# Peripherals.net
KiCad netlist of a schematic drawn in Altium Designer
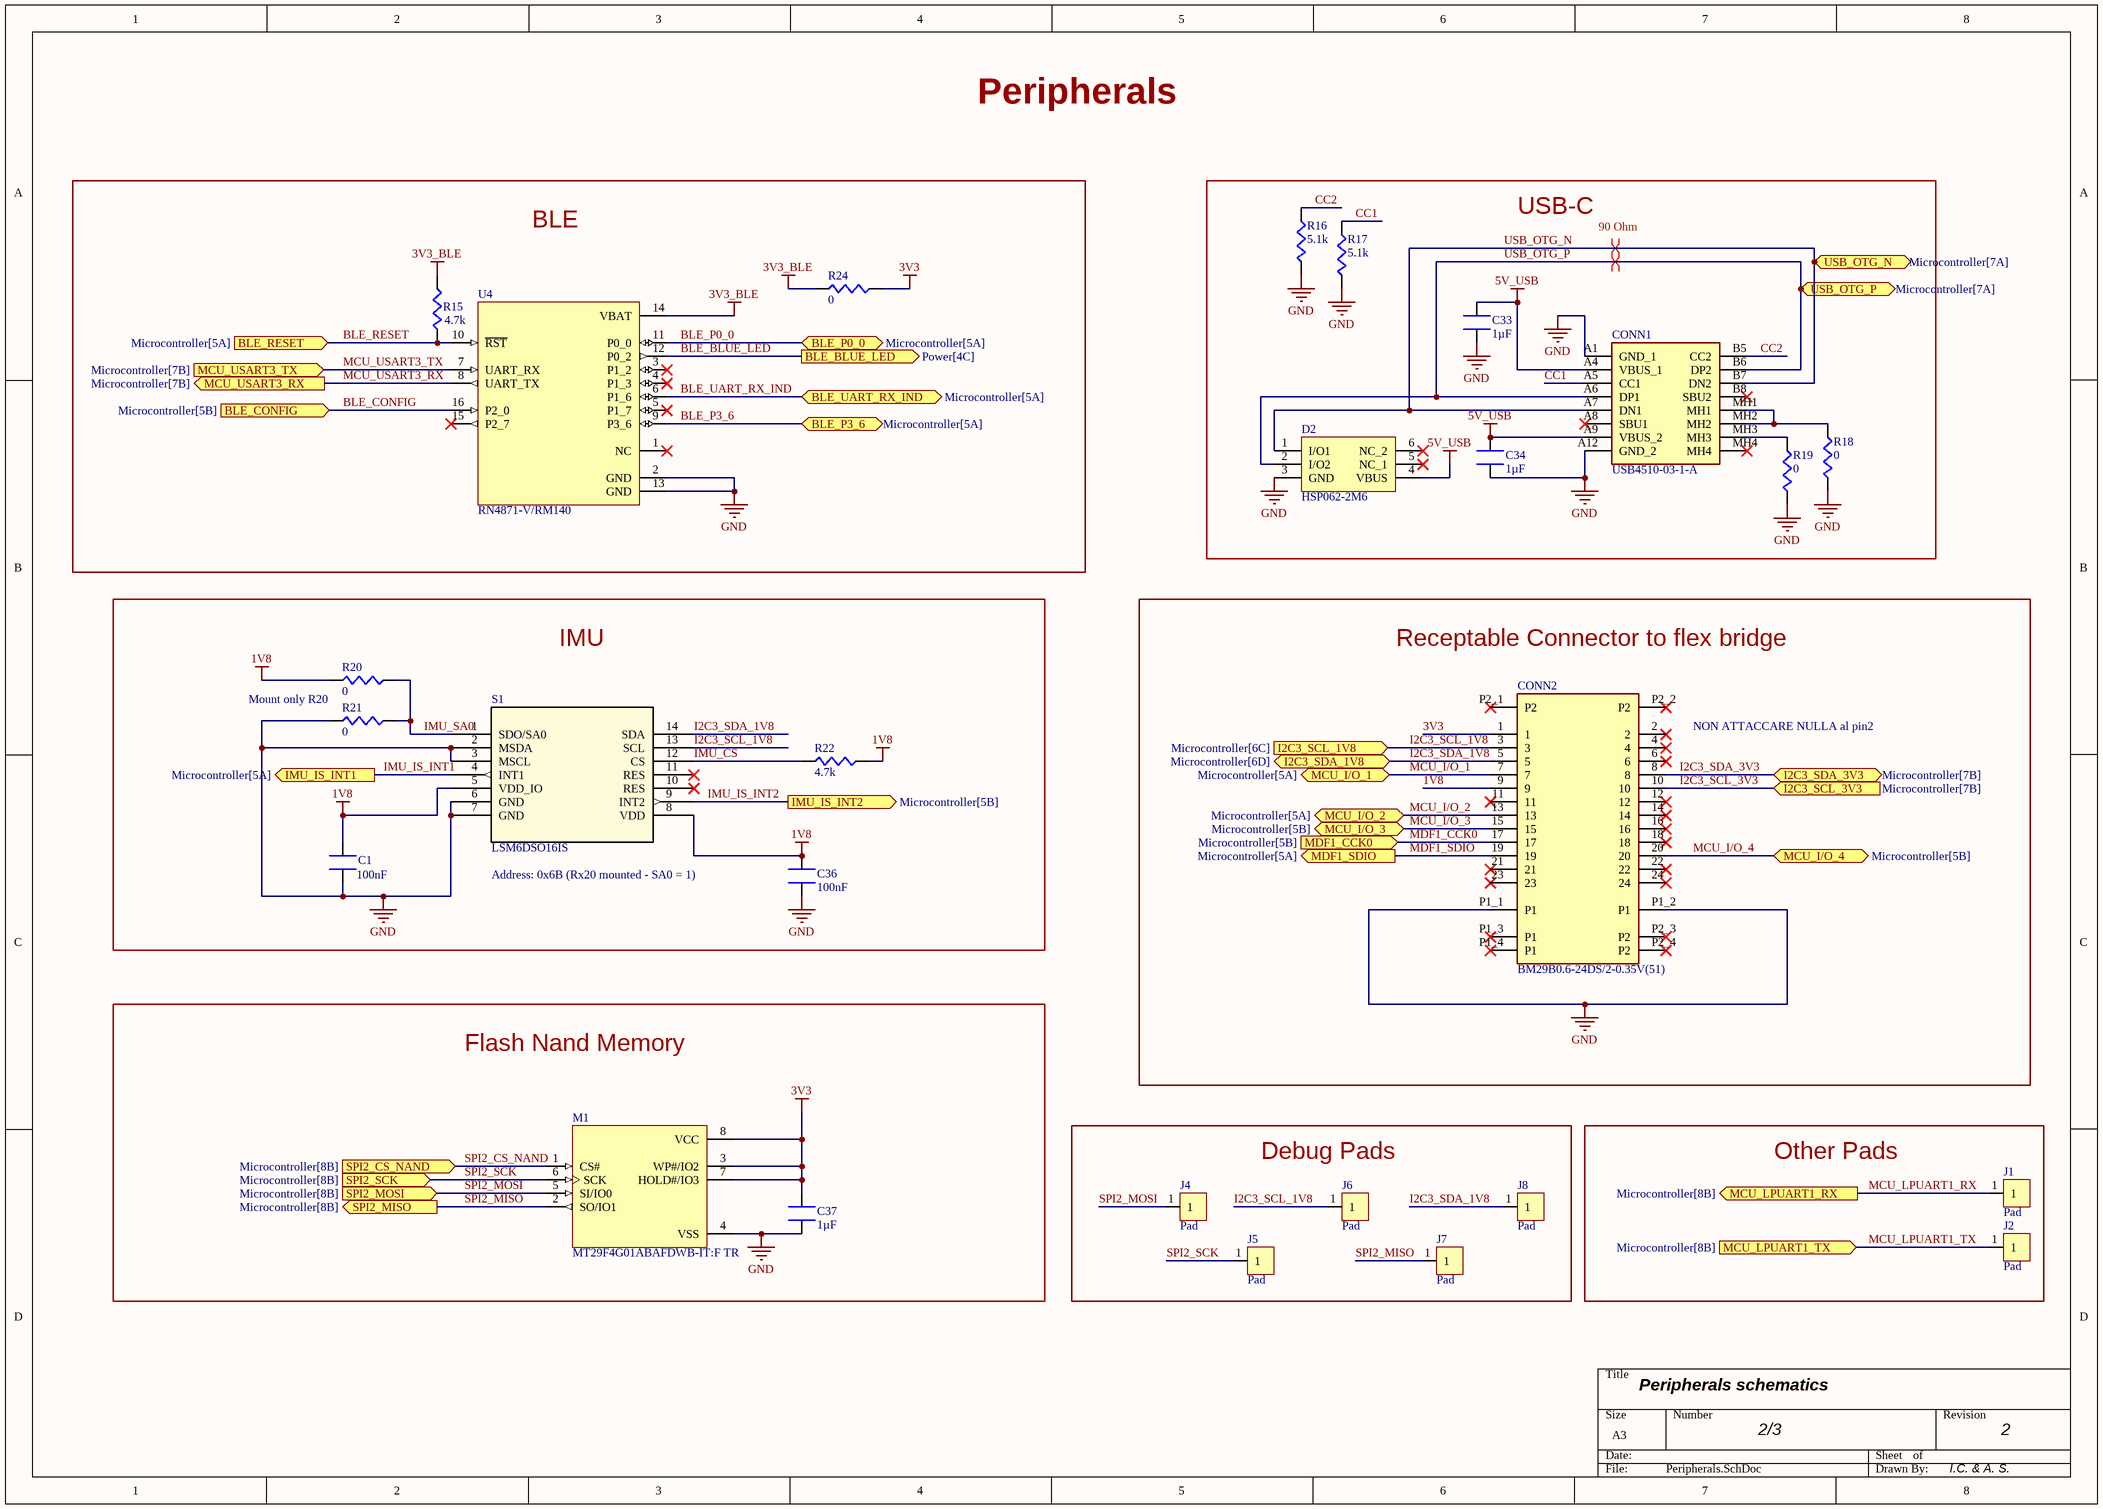
[diagram p0: Peripherals.SchDoc]

(export (version "E")
  (design (tool "Eeschema 10.0.6"))
  (components
    (comp (ref "C1")
      (value "100nF")
      (footprint "Chip2PinSM127P600-8N")
      (fields (field (name "Comment") "0201ZD104KAT2A"))
      (libsource (lib "Workspace LAB SEL") (part "Generic capacitor"))
    )
    (comp (ref "C33")
      (value "1µF")
      (footprint "Chip2PinSM127P600-8N")
      (fields (field (name "Comment") "CL03A105KP3NSNC"))
      (libsource (lib "Workspace LAB SEL") (part "Generic capacitor"))
    )
    (comp (ref "C34")
      (value "1µF")
      (footprint "Chip2PinSM127P600-8N")
      (fields (field (name "Comment") "CL03A105KP3NSNC"))
      (libsource (lib "Workspace LAB SEL") (part "Generic capacitor"))
    )
    (comp (ref "C36")
      (value "100nF")
      (footprint "Chip2PinSM127P600-8N")
      (fields (field (name "Comment") "0201ZD104KAT2A"))
      (libsource (lib "Workspace LAB SEL") (part "Generic capacitor"))
    )
    (comp (ref "C37")
      (value "1µF")
      (footprint "Chip2PinSM127P600-8N")
      (fields (field (name "Comment") "CL03A105KP3NSNC"))
      (libsource (lib "Workspace LAB SEL") (part "Generic capacitor"))
    )
    (comp (ref "CONN1")
      (value "USB4510-03-1-A")
      (footprint "USB4510-03-1-A-Footprint-1")
      (description "Connettori USB USB C Rec 16P 3u\" Mid Mnt 1.6mm O-set SMT L = 6.5mm S-Spring")
      (libsource (lib "Workspace LAB SEL") (part "New symbol 1"))
    )
    (comp (ref "CONN2")
      (value "BM29B0.6-24DS/2-0.35V(51)")
      (footprint "BM29B0.6-24DS_2-0.35V(51)-Footprint-1")
      (description "Connector Receptacle 26 Pos (24+2) SMD")
      (libsource (lib "Workspace LAB SEL") (part "BM29B0.6-24DS_2-0.35V(51)-Symbol-1"))
    )
    (comp (ref "D2")
      (value "HSP062-2M6")
      (footprint "HSP062-2M6-Footprint-1")
      (description "TVS DIODE 3VWM 18VC 6UQFN / ESD Suppressor Diode Array Uni-Dir 3V 6-Pin UQFN T/R")
      (libsource (lib "Workspace LAB SEL") (part "HSP062-2M6"))
    )
    (comp (ref "J1")
      (value "Pad")
      (footprint "Pad-Footprint-1")
      (description "Pad to connect external electrodes or sensors. Choose the right footprint.")
      (libsource (lib "Workspace LAB SEL") (part "Pad-Symbol-1"))
    )
    (comp (ref "J2")
      (value "Pad")
      (footprint "Pad-Footprint-1")
      (description "Pad to connect external electrodes or sensors. Choose the right footprint.")
      (libsource (lib "Workspace LAB SEL") (part "Pad-Symbol-1"))
    )
    (comp (ref "J4")
      (value "Pad")
      (footprint "Pad-Footprint-1")
      (description "Pad to connect external electrodes or sensors. Choose the right footprint.")
      (libsource (lib "Workspace LAB SEL") (part "Pad-Symbol-1"))
    )
    (comp (ref "J5")
      (value "Pad")
      (footprint "Pad-Footprint-1")
      (description "Pad to connect external electrodes or sensors. Choose the right footprint.")
      (libsource (lib "Workspace LAB SEL") (part "Pad-Symbol-1"))
    )
    (comp (ref "J6")
      (value "Pad")
      (footprint "Pad-Footprint-1")
      (description "Pad to connect external electrodes or sensors. Choose the right footprint.")
      (libsource (lib "Workspace LAB SEL") (part "Pad-Symbol-1"))
    )
    (comp (ref "J7")
      (value "Pad")
      (footprint "Pad-Footprint-1")
      (description "Pad to connect external electrodes or sensors. Choose the right footprint.")
      (libsource (lib "Workspace LAB SEL") (part "Pad-Symbol-1"))
    )
    (comp (ref "J8")
      (value "Pad")
      (footprint "Pad-Footprint-1")
      (description "Pad to connect external electrodes or sensors. Choose the right footprint.")
      (libsource (lib "Workspace LAB SEL") (part "Pad-Symbol-1"))
    )
    (comp (ref "M1")
      (value "MT29F4G01ABAFDWB-IT:F TR")
      (footprint "MT29F4G01ABAFDWB-IT:F TR-Footprint-1")
      (description "Active Non-Volatile SPI FLASH ic memory -40C~85C TA 2.7V~3.6V 4Gb 4G x 1")
      (libsource (lib "Workspace LAB SEL") (part "MT29F4G01ABAFDWB-IT{colon}F TR-Symbol-1"))
    )
    (comp (ref "R15")
      (value "4.7k")
      (footprint "RESC1005X04N")
      (description "SMD Chip Resistor, 4.7 kOhm, ± 1%, 63 mW, 0402 [1005 Metric], Thick Film, General Purpose")
      (fields (field (name "Comment") "CRCW04024K70FKED"))
      (libsource (lib "Workspace LAB SEL") (part "Generic resistor"))
    )
    (comp (ref "R16")
      (value "5.1k")
      (footprint "Chip2PinSM127P600-8N")
      (fields
        (field (name "POWER") "50mW")
        (field (name "TOLERANCE") "1%")
        (field (name "Comment") "ERJ-1GNF5101C")
      )
      (libsource (lib "Workspace LAB SEL") (part "Generic resistor"))
    )
    (comp (ref "R17")
      (value "5.1k")
      (footprint "Chip2PinSM127P600-8N")
      (fields
        (field (name "POWER") "50mW")
        (field (name "TOLERANCE") "1%")
        (field (name "Comment") "ERJ-1GNF5101C")
      )
      (libsource (lib "Workspace LAB SEL") (part "Generic resistor"))
    )
    (comp (ref "R18")
      (value "0")
      (footprint "Chip2PinSM127P600-8N")
      (description "Fixed Resistor, Metal Glaze/thick Film, 0.05W, 0ohm, Surface Mount, 0201")
      (fields (field (name "POWER") "50mW") (field (name "Comment") "CRCW02010000Z0ED"))
      (libsource (lib "Workspace LAB SEL") (part "Generic resistor"))
    )
    (comp (ref "R19")
      (value "0")
      (footprint "Chip2PinSM127P600-8N")
      (description "Fixed Resistor, Metal Glaze/thick Film, 0.05W, 0ohm, Surface Mount, 0201")
      (fields (field (name "POWER") "50mW") (field (name "Comment") "CRCW02010000Z0ED"))
      (libsource (lib "Workspace LAB SEL") (part "Generic resistor"))
    )
    (comp (ref "R20")
      (value "0")
      (footprint "Chip2PinSM127P600-8N")
      (description "Fixed Resistor, Metal Glaze/thick Film, 0.05W, 0ohm, Surface Mount, 0201")
      (fields (field (name "POWER") "50mW") (field (name "Comment") "CRCW02010000Z0ED"))
      (libsource (lib "Workspace LAB SEL") (part "Generic resistor"))
    )
    (comp (ref "R21")
      (value "0")
      (footprint "Chip2PinSM127P600-8N")
      (description "Fixed Resistor, Metal Glaze/thick Film, 0.05W, 0ohm, Surface Mount, 0201")
      (fields (field (name "POWER") "50mW") (field (name "Comment") "CRCW02010000Z0ED"))
      (libsource (lib "Workspace LAB SEL") (part "Generic resistor"))
    )
    (comp (ref "R22")
      (value "4.7k")
      (footprint "Chip2PinSM127P600-8N")
      (fields
        (field (name "TOLERANCE") "5%")
        (field (name "POWER") "50mW")
        (field (name "Comment") "CR0201-JW-472GLF")
      )
      (libsource (lib "Workspace LAB SEL") (part "Generic resistor"))
    )
    (comp (ref "R24")
      (value "0")
      (footprint "Chip2PinSM127P600-8N")
      (description "Fixed Resistor, Metal Glaze/thick Film, 0.05W, 0ohm, Surface Mount, 0201")
      (fields (field (name "POWER") "50mW") (field (name "Comment") "CRCW02010000Z0ED"))
      (libsource (lib "Workspace LAB SEL") (part "Generic resistor"))
    )
    (comp (ref "S1")
      (value "LSM6DSO16IS")
      (footprint "LSM6DSO16IS-Footprint-1")
      (description "IMU 6-axis with Intelligent Sensor Process Unit")
      (libsource (lib "Workspace LAB SEL") (part "LSM6DSO16IS"))
    )
    (comp (ref "U4")
      (value "RN4871-V/RM140")
      (footprint "RN4871-V_RM118-Footprint-1")
      (libsource (lib "Workspace LAB SEL") (part "RN4871-V_RM140"))
    )
  )
  (nets
    (net (code "1") (name "/BLE_BLUE_LED") (class "Default")
      (node (ref "U4") (pin "12") (pinfunction "P0_2_12") (pintype "output"))
    )
    (net (code "2") (name "/BLE_CONFIG") (class "Default")
      (node (ref "U4") (pin "16") (pinfunction "P2_0_16") (pintype "input"))
    )
    (net (code "3") (name "/BLE_P0_0") (class "Default")
      (node (ref "U4") (pin "11") (pinfunction "P0_0_11") (pintype "bidirectional"))
    )
    (net (code "4") (name "/BLE_P3_6") (class "Default")
      (node (ref "U4") (pin "9") (pinfunction "P3_6_9") (pintype "bidirectional"))
    )
    (net (code "5") (name "/BLE_RESET") (class "Default")
      (node (ref "R15") (pin "1") (pinfunction "1_1") (pintype "passive"))
      (node (ref "U4") (pin "10") (pinfunction "~{RST}_10") (pintype "input"))
    )
    (net (code "6") (name "/BLE_UART_RX_IND") (class "Default")
      (node (ref "U4") (pin "6") (pinfunction "P1_6_6") (pintype "bidirectional"))
    )
    (net (code "7") (name "/CC1") (class "Default")
      (node (ref "CONN1") (pin "A5") (pinfunction "CC1_A5") (pintype "passive"))
      (node (ref "R17") (pin "2") (pinfunction "2_2") (pintype "passive"))
    )
    (net (code "8") (name "/CC2") (class "Default")
      (node (ref "CONN1") (pin "B5") (pinfunction "CC2_B5") (pintype "passive"))
      (node (ref "R16") (pin "2") (pinfunction "2_2") (pintype "passive"))
    )
    (net (code "9") (name "/I2C3_SCL_1V8") (class "Default")
      (node (ref "CONN2") (pin "3") (pinfunction "3_3") (pintype "passive"))
      (node (ref "J6") (pin "1") (pinfunction "1_1") (pintype "passive"))
      (node (ref "S1") (pin "13") (pinfunction "SCL_13") (pintype "passive"))
    )
    (net (code "10") (name "/I2C3_SCL_3V3") (class "Default")
      (node (ref "CONN2") (pin "10") (pinfunction "10_10") (pintype "passive"))
    )
    (net (code "11") (name "/I2C3_SDA_1V8") (class "Default")
      (node (ref "CONN2") (pin "5") (pinfunction "5_5") (pintype "passive"))
      (node (ref "J8") (pin "1") (pinfunction "1_1") (pintype "passive"))
      (node (ref "S1") (pin "14") (pinfunction "SDA_14") (pintype "passive"))
    )
    (net (code "12") (name "/I2C3_SDA_3V3") (class "Default")
      (node (ref "CONN2") (pin "8") (pinfunction "8_8") (pintype "passive"))
    )
    (net (code "13") (name "/IMU_CS") (class "Default")
      (node (ref "R22") (pin "1") (pinfunction "1_1") (pintype "passive"))
      (node (ref "S1") (pin "12") (pinfunction "CS_12") (pintype "passive"))
    )
    (net (code "14") (name "/IMU_IS_INT1") (class "Default")
      (node (ref "S1") (pin "4") (pinfunction "INT1_4") (pintype "output"))
    )
    (net (code "15") (name "/IMU_IS_INT2") (class "Default")
      (node (ref "S1") (pin "9") (pinfunction "INT2_9") (pintype "output"))
    )
    (net (code "16") (name "/IMU_SA0") (class "Default")
      (node (ref "R20") (pin "2") (pinfunction "2_2") (pintype "passive"))
      (node (ref "R21") (pin "2") (pinfunction "2_2") (pintype "passive"))
      (node (ref "S1") (pin "1") (pinfunction "SDO/SA0_1") (pintype "passive"))
    )
    (net (code "17") (name "/MCU_I{slash}O_1") (class "Default")
      (node (ref "CONN2") (pin "7") (pinfunction "7_7") (pintype "passive"))
    )
    (net (code "18") (name "/MCU_I{slash}O_2") (class "Default")
      (node (ref "CONN2") (pin "13") (pinfunction "13_13") (pintype "passive"))
    )
    (net (code "19") (name "/MCU_I{slash}O_3") (class "Default")
      (node (ref "CONN2") (pin "15") (pinfunction "15_15") (pintype "passive"))
    )
    (net (code "20") (name "/MCU_I{slash}O_4") (class "Default")
      (node (ref "CONN2") (pin "20") (pinfunction "20_20") (pintype "passive"))
    )
    (net (code "21") (name "/MCU_LPUART1_RX") (class "Default")
      (node (ref "J1") (pin "1") (pinfunction "1_1") (pintype "passive"))
    )
    (net (code "22") (name "/MCU_LPUART1_TX") (class "Default")
      (node (ref "J2") (pin "1") (pinfunction "1_1") (pintype "passive"))
    )
    (net (code "23") (name "/MCU_USART3_RX") (class "Default")
      (node (ref "U4") (pin "8") (pinfunction "UART_TX_8") (pintype "output"))
    )
    (net (code "24") (name "/MCU_USART3_TX") (class "Default")
      (node (ref "U4") (pin "7") (pinfunction "UART_RX_7") (pintype "input"))
    )
    (net (code "25") (name "/MDF1_CCK0") (class "Default")
      (node (ref "CONN2") (pin "17") (pinfunction "17_17") (pintype "passive"))
    )
    (net (code "26") (name "/MDF1_SDIO") (class "Default")
      (node (ref "CONN2") (pin "19") (pinfunction "19_19") (pintype "passive"))
    )
    (net (code "27") (name "/SPI2_CS_NAND") (class "Default")
      (node (ref "M1") (pin "1") (pinfunction "CS#_1") (pintype "input"))
    )
    (net (code "28") (name "/SPI2_MISO") (class "Default")
      (node (ref "J7") (pin "1") (pinfunction "1_1") (pintype "passive"))
      (node (ref "M1") (pin "2") (pinfunction "SO/IO1_2") (pintype "output"))
    )
    (net (code "29") (name "/SPI2_MOSI") (class "Default")
      (node (ref "J4") (pin "1") (pinfunction "1_1") (pintype "passive"))
      (node (ref "M1") (pin "5") (pinfunction "SI/IO0_5") (pintype "input"))
    )
    (net (code "30") (name "/SPI2_SCK") (class "Default")
      (node (ref "J5") (pin "1") (pinfunction "1_1") (pintype "passive"))
      (node (ref "M1") (pin "6") (pinfunction "SCK_6") (pintype "input"))
    )
    (net (code "31") (name "/USB_OTG_N") (class "Default")
      (node (ref "CONN1") (pin "A7") (pinfunction "DN1_A7") (pintype "passive"))
      (node (ref "CONN1") (pin "B7") (pinfunction "DN2_B7") (pintype "passive"))
      (node (ref "D2") (pin "1") (pinfunction "I/O1_1") (pintype "passive"))
    )
    (net (code "32") (name "/USB_OTG_P") (class "Default")
      (node (ref "CONN1") (pin "A6") (pinfunction "DP1_A6") (pintype "passive"))
      (node (ref "CONN1") (pin "B6") (pinfunction "DP2_B6") (pintype "passive"))
      (node (ref "D2") (pin "2") (pinfunction "I/O2_2") (pintype "passive"))
    )
    (net (code "33") (name "1V8") (class "Default")
      (node (ref "C1") (pin "2") (pinfunction "2_2") (pintype "passive"))
      (node (ref "C36") (pin "2") (pinfunction "2_2") (pintype "passive"))
      (node (ref "CONN2") (pin "9") (pinfunction "9_9") (pintype "passive"))
      (node (ref "R20") (pin "1") (pinfunction "1_1") (pintype "passive"))
      (node (ref "R22") (pin "2") (pinfunction "2_2") (pintype "passive"))
      (node (ref "S1") (pin "5") (pinfunction "VDD_IO_5") (pintype "power_in"))
      (node (ref "S1") (pin "8") (pinfunction "VDD_8") (pintype "power_in"))
    )
    (net (code "34") (name "3V3") (class "Default")
      (node (ref "C37") (pin "2") (pinfunction "2_2") (pintype "passive"))
      (node (ref "CONN2") (pin "1") (pinfunction "1_1") (pintype "passive"))
      (node (ref "M1") (pin "3") (pinfunction "WP#/IO2_3") (pintype "power_in"))
      (node (ref "M1") (pin "7") (pinfunction "HOLD#/IO3_7") (pintype "power_in"))
      (node (ref "M1") (pin "8") (pinfunction "VCC_8") (pintype "power_in"))
      (node (ref "R24") (pin "2") (pinfunction "2_2") (pintype "passive"))
    )
    (net (code "35") (name "3V3_BLE") (class "Default")
      (node (ref "R15") (pin "2") (pinfunction "2_2") (pintype "passive"))
      (node (ref "R24") (pin "1") (pinfunction "1_1") (pintype "passive"))
      (node (ref "U4") (pin "14") (pinfunction "VBAT_14") (pintype "power_in"))
    )
    (net (code "36") (name "5V_USB") (class "Default")
      (node (ref "C33") (pin "2") (pinfunction "2_2") (pintype "passive"))
      (node (ref "C34") (pin "2") (pinfunction "2_2") (pintype "passive"))
      (node (ref "CONN1") (pin "A4") (pinfunction "VBUS_1_A4") (pintype "passive"))
      (node (ref "CONN1") (pin "A9") (pinfunction "VBUS_2_A9") (pintype "passive"))
      (node (ref "D2") (pin "4") (pinfunction "VBUS_4") (pintype "passive"))
    )
    (net (code "37") (name "GND") (class "Default")
      (node (ref "C1") (pin "1") (pinfunction "1_1") (pintype "passive"))
      (node (ref "C33") (pin "1") (pinfunction "1_1") (pintype "passive"))
      (node (ref "C34") (pin "1") (pinfunction "1_1") (pintype "passive"))
      (node (ref "C36") (pin "1") (pinfunction "1_1") (pintype "passive"))
      (node (ref "C37") (pin "1") (pinfunction "1_1") (pintype "passive"))
      (node (ref "CONN1") (pin "A1") (pinfunction "GND_1_A1") (pintype "passive"))
      (node (ref "CONN1") (pin "A12") (pinfunction "GND_2_A12") (pintype "passive"))
      (node (ref "CONN2") (pin "P1_1") (pinfunction "P1_P1_1") (pintype "power_in"))
      (node (ref "CONN2") (pin "P1_2") (pinfunction "P1_P1_2") (pintype "power_in"))
      (node (ref "D2") (pin "3") (pinfunction "GND_3") (pintype "passive"))
      (node (ref "M1") (pin "4") (pinfunction "VSS_4") (pintype "power_in"))
      (node (ref "R16") (pin "1") (pinfunction "1_1") (pintype "passive"))
      (node (ref "R17") (pin "1") (pinfunction "1_1") (pintype "passive"))
      (node (ref "R18") (pin "1") (pinfunction "1_1") (pintype "passive"))
      (node (ref "R19") (pin "1") (pinfunction "1_1") (pintype "passive"))
      (node (ref "R21") (pin "1") (pinfunction "1_1") (pintype "passive"))
      (node (ref "S1") (pin "2") (pinfunction "MSDA_2") (pintype "passive"))
      (node (ref "S1") (pin "3") (pinfunction "MSCL_3") (pintype "passive"))
      (node (ref "S1") (pin "6") (pinfunction "GND_6") (pintype "power_in"))
      (node (ref "S1") (pin "7") (pinfunction "GND_7") (pintype "power_in"))
      (node (ref "U4") (pin "13") (pinfunction "GND_13") (pintype "power_in"))
      (node (ref "U4") (pin "2") (pinfunction "GND_2") (pintype "power_in"))
    )
    (net (code "38") (name "Net-(CONN1-PadMH1)") (class "Default")
      (node (ref "CONN1") (pin "MH1") (pinfunction "MH1_MH1") (pintype "passive"))
      (node (ref "CONN1") (pin "MH2") (pinfunction "MH2_MH2") (pintype "passive"))
      (node (ref "R18") (pin "2") (pinfunction "2_2") (pintype "passive"))
    )
    (net (code "39") (name "Net-(CONN1-PadMH3)") (class "Default")
      (node (ref "CONN1") (pin "MH3") (pinfunction "MH3_MH3") (pintype "passive"))
      (node (ref "R19") (pin "2") (pinfunction "2_2") (pintype "passive"))
    )
    (net (code "40") (name "unconnected-(CONN1-PadMH4)") (class "Default")
      (node (ref "CONN1") (pin "MH4") (pinfunction "MH4_MH4") (pintype "passive+no_connect"))
    )
    (net (code "41") (name "unconnected-(CONN1-SBU1-PadA8)") (class "Default")
      (node (ref "CONN1") (pin "A8") (pinfunction "SBU1_A8") (pintype "passive+no_connect"))
    )
    (net (code "42") (name "unconnected-(CONN1-SBU2-PadB8)") (class "Default")
      (node (ref "CONN1") (pin "B8") (pinfunction "SBU2_B8") (pintype "passive+no_connect"))
    )
    (net (code "43") (name "unconnected-(CONN2-P1-PadP1_3)") (class "Default")
      (node (ref "CONN2") (pin "P1_3") (pinfunction "P1_P1_3") (pintype "power_in+no_connect"))
    )
    (net (code "44") (name "unconnected-(CONN2-P1-PadP1_4)") (class "Default")
      (node (ref "CONN2") (pin "P1_4") (pinfunction "P1_P1_4") (pintype "power_in+no_connect"))
    )
    (net (code "45") (name "unconnected-(CONN2-P2-PadP2_1)") (class "Default")
      (node (ref "CONN2") (pin "P2_1") (pinfunction "P2_P2_1") (pintype "power_in+no_connect"))
    )
    (net (code "46") (name "unconnected-(CONN2-P2-PadP2_2)") (class "Default")
      (node (ref "CONN2") (pin "P2_2") (pinfunction "P2_P2_2") (pintype "power_in+no_connect"))
    )
    (net (code "47") (name "unconnected-(CONN2-P2-PadP2_3)") (class "Default")
      (node (ref "CONN2") (pin "P2_3") (pinfunction "P2_P2_3") (pintype "power_in+no_connect"))
    )
    (net (code "48") (name "unconnected-(CONN2-P2-PadP2_4)") (class "Default")
      (node (ref "CONN2") (pin "P2_4") (pinfunction "P2_P2_4") (pintype "power_in+no_connect"))
    )
    (net (code "49") (name "unconnected-(CONN2-Pad2)") (class "Default")
      (node (ref "CONN2") (pin "2") (pinfunction "2_2") (pintype "passive+no_connect"))
    )
    (net (code "50") (name "unconnected-(CONN2-Pad4)") (class "Default")
      (node (ref "CONN2") (pin "4") (pinfunction "4_4") (pintype "passive+no_connect"))
    )
    (net (code "51") (name "unconnected-(CONN2-Pad6)") (class "Default")
      (node (ref "CONN2") (pin "6") (pinfunction "6_6") (pintype "passive+no_connect"))
    )
    (net (code "52") (name "unconnected-(CONN2-Pad11)") (class "Default")
      (node (ref "CONN2") (pin "11") (pinfunction "11_11") (pintype "passive+no_connect"))
    )
    (net (code "53") (name "unconnected-(CONN2-Pad12)") (class "Default")
      (node (ref "CONN2") (pin "12") (pinfunction "12_12") (pintype "passive+no_connect"))
    )
    (net (code "54") (name "unconnected-(CONN2-Pad14)") (class "Default")
      (node (ref "CONN2") (pin "14") (pinfunction "14_14") (pintype "passive+no_connect"))
    )
    (net (code "55") (name "unconnected-(CONN2-Pad16)") (class "Default")
      (node (ref "CONN2") (pin "16") (pinfunction "16_16") (pintype "passive+no_connect"))
    )
    (net (code "56") (name "unconnected-(CONN2-Pad18)") (class "Default")
      (node (ref "CONN2") (pin "18") (pinfunction "18_18") (pintype "passive+no_connect"))
    )
    (net (code "57") (name "unconnected-(CONN2-Pad21)") (class "Default")
      (node (ref "CONN2") (pin "21") (pinfunction "21_21") (pintype "passive+no_connect"))
    )
    (net (code "58") (name "unconnected-(CONN2-Pad22)") (class "Default")
      (node (ref "CONN2") (pin "22") (pinfunction "22_22") (pintype "passive+no_connect"))
    )
    (net (code "59") (name "unconnected-(CONN2-Pad23)") (class "Default")
      (node (ref "CONN2") (pin "23") (pinfunction "23_23") (pintype "passive+no_connect"))
    )
    (net (code "60") (name "unconnected-(CONN2-Pad24)") (class "Default")
      (node (ref "CONN2") (pin "24") (pinfunction "24_24") (pintype "passive+no_connect"))
    )
    (net (code "61") (name "unconnected-(D2-NC_1-Pad5)") (class "Default")
      (node (ref "D2") (pin "5") (pinfunction "NC_1_5") (pintype "passive+no_connect"))
    )
    (net (code "62") (name "unconnected-(D2-NC_2-Pad6)") (class "Default")
      (node (ref "D2") (pin "6") (pinfunction "NC_2_6") (pintype "passive+no_connect"))
    )
    (net (code "63") (name "unconnected-(S1-RES-Pad10)") (class "Default")
      (node (ref "S1") (pin "10") (pinfunction "RES_10") (pintype "passive+no_connect"))
    )
    (net (code "64") (name "unconnected-(S1-RES-Pad11)") (class "Default")
      (node (ref "S1") (pin "11") (pinfunction "RES_11") (pintype "passive+no_connect"))
    )
    (net (code "65") (name "unconnected-(U4-NC-Pad1)") (class "Default")
      (node (ref "U4") (pin "1") (pinfunction "NC_1") (pintype "passive+no_connect"))
    )
    (net (code "66") (name "unconnected-(U4-P1_2-Pad3)") (class "Default")
      (node (ref "U4") (pin "3") (pinfunction "P1_2_3") (pintype "bidirectional+no_connect"))
    )
    (net (code "67") (name "unconnected-(U4-P1_3-Pad4)") (class "Default")
      (node (ref "U4") (pin "4") (pinfunction "P1_3_4") (pintype "bidirectional+no_connect"))
    )
    (net (code "68") (name "unconnected-(U4-P1_7-Pad5)") (class "Default")
      (node (ref "U4") (pin "5") (pinfunction "P1_7_5") (pintype "bidirectional+no_connect"))
    )
    (net (code "69") (name "unconnected-(U4-P2_7-Pad15)") (class "Default")
      (node (ref "U4") (pin "15") (pinfunction "P2_7_15") (pintype "output+no_connect"))
    )
  )
)
